# w65c265sxb_controller.net
KiCad netlist of a schematic drawn in EAGLE
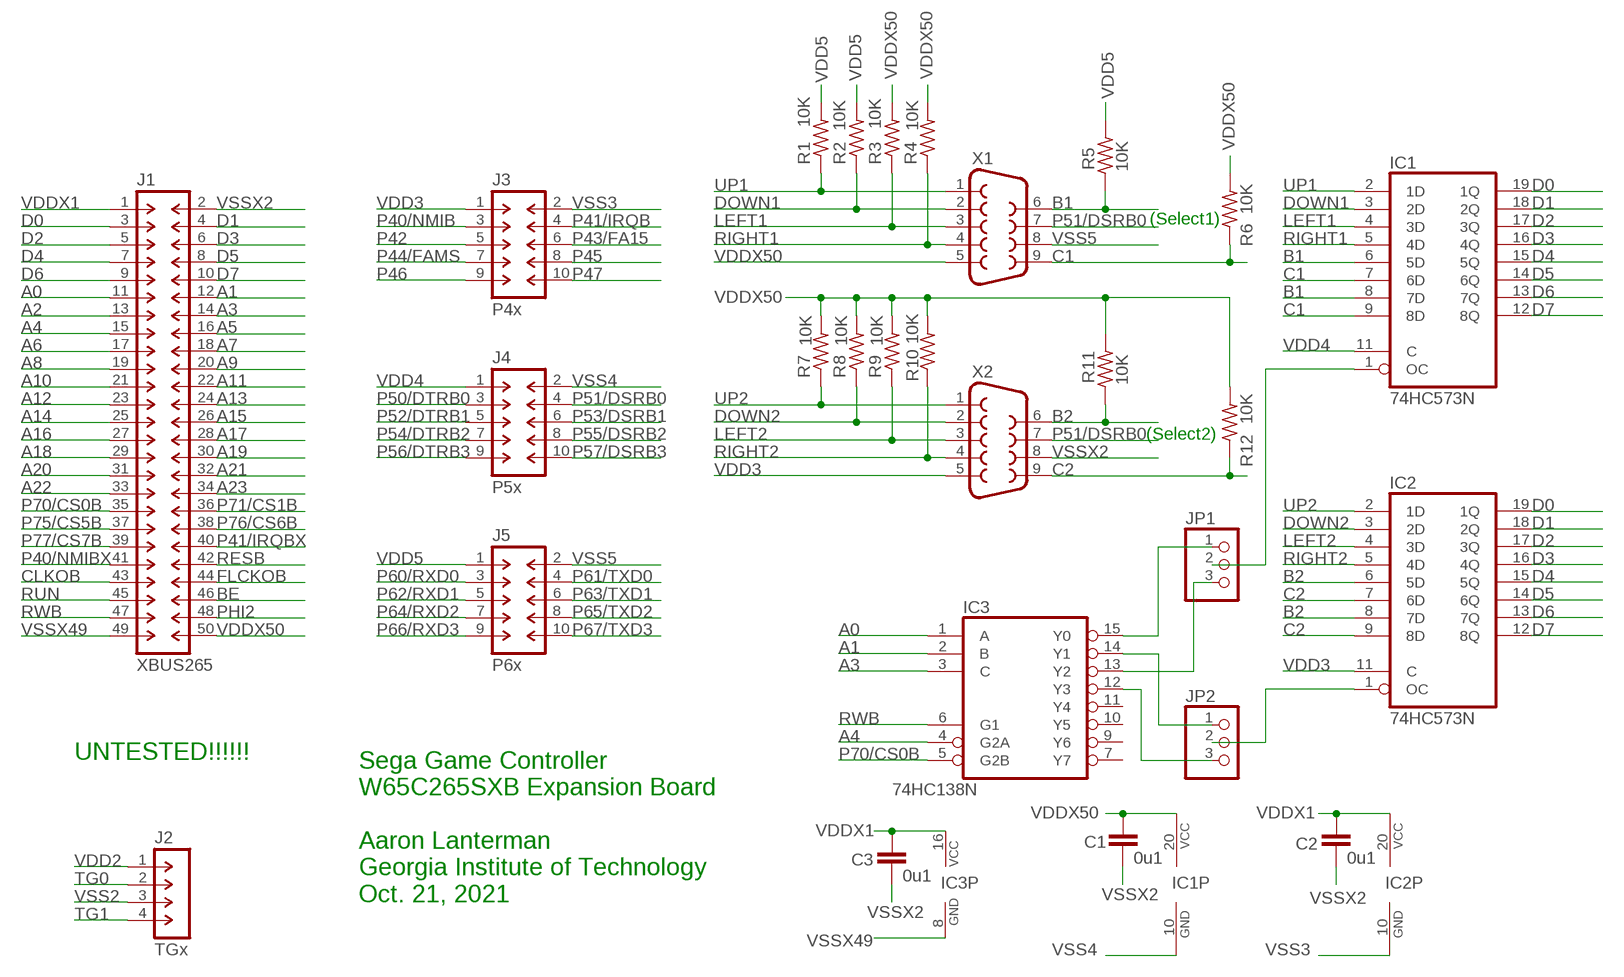
[diagram p0: schematic, sheet 1]

(export (version "E")
  (design (tool "Eeschema 10.0.6"))
  (components
    (comp (ref "C1")
      (value "0u1")
      (footprint "eagle-import:C050-025X075-AARON")
      (libsource (lib "eagle-import") (part "C-EU050-025X075-AARON"))
    )
    (comp (ref "C2")
      (value "0u1")
      (footprint "eagle-import:C050-025X075-AARON")
      (libsource (lib "eagle-import") (part "C-EU050-025X075-AARON"))
    )
    (comp (ref "C3")
      (value "0u1")
      (footprint "eagle-import:C050-025X075-AARON")
      (libsource (lib "eagle-import") (part "C-EU050-025X075-AARON"))
    )
    (comp (ref "IC1")
      (value "74HC573N")
      (footprint "eagle-import:DIL20")
      (libsource (lib "eagle-import") (part "74573NHC"))
    )
    (comp (ref "IC2")
      (value "74HC573N")
      (footprint "eagle-import:DIL20")
      (libsource (lib "eagle-import") (part "74573NHC"))
    )
    (comp (ref "IC3")
      (value "74HC138N")
      (footprint "eagle-import:DIL16")
      (libsource (lib "eagle-import") (part "74138NHC"))
    )
    (comp (ref "J1")
      (value "XBUS265")
      (footprint "eagle-import:DIL-100-2X25")
      (libsource (lib "eagle-import") (part "M-2X25-DIL-100"))
    )
    (comp (ref "J2")
      (value "TGx")
      (footprint "eagle-import:SIP-100-04-40")
      (libsource (lib "eagle-import") (part "M-1X04-SIP-100-40"))
    )
    (comp (ref "J3")
      (value "P4x")
      (footprint "eagle-import:DIL-100-2X05")
      (libsource (lib "eagle-import") (part "M-2X05-DIL-100"))
    )
    (comp (ref "J4")
      (value "P5x")
      (footprint "eagle-import:DIL-100-2X05")
      (libsource (lib "eagle-import") (part "M-2X05-DIL-100"))
    )
    (comp (ref "J5")
      (value "P6x")
      (footprint "eagle-import:DIL-100-2X05")
      (libsource (lib "eagle-import") (part "M-2X05-DIL-100"))
    )
    (comp (ref "JP1")
      (value "PINHD-1X3")
      (footprint "eagle-import:1X03")
      (libsource (lib "eagle-import") (part "PINHD-1X3"))
    )
    (comp (ref "JP2")
      (value "PINHD-1X3")
      (footprint "eagle-import:1X03")
      (libsource (lib "eagle-import") (part "PINHD-1X3"))
    )
    (comp (ref "R1")
      (value "10K")
      (footprint "eagle-import:0207_10")
      (libsource (lib "eagle-import") (part "R-US_0207/10"))
    )
    (comp (ref "R2")
      (value "10K")
      (footprint "eagle-import:0207_10")
      (libsource (lib "eagle-import") (part "R-US_0207/10"))
    )
    (comp (ref "R3")
      (value "10K")
      (footprint "eagle-import:0207_10")
      (libsource (lib "eagle-import") (part "R-US_0207/10"))
    )
    (comp (ref "R4")
      (value "10K")
      (footprint "eagle-import:0207_10")
      (libsource (lib "eagle-import") (part "R-US_0207/10"))
    )
    (comp (ref "R5")
      (value "10K")
      (footprint "eagle-import:0207_10")
      (libsource (lib "eagle-import") (part "R-US_0207/10"))
    )
    (comp (ref "R6")
      (value "10K")
      (footprint "eagle-import:0207_10")
      (libsource (lib "eagle-import") (part "R-US_0207/10"))
    )
    (comp (ref "R7")
      (value "10K")
      (footprint "eagle-import:0207_10")
      (libsource (lib "eagle-import") (part "R-US_0207/10"))
    )
    (comp (ref "R8")
      (value "10K")
      (footprint "eagle-import:0207_10")
      (libsource (lib "eagle-import") (part "R-US_0207/10"))
    )
    (comp (ref "R9")
      (value "10K")
      (footprint "eagle-import:0207_10")
      (libsource (lib "eagle-import") (part "R-US_0207/10"))
    )
    (comp (ref "R10")
      (value "10K")
      (footprint "eagle-import:0207_10")
      (libsource (lib "eagle-import") (part "R-US_0207/10"))
    )
    (comp (ref "R11")
      (value "10K")
      (footprint "eagle-import:0207_10")
      (libsource (lib "eagle-import") (part "R-US_0207/10"))
    )
    (comp (ref "R12")
      (value "10K")
      (footprint "eagle-import:0207_10")
      (libsource (lib "eagle-import") (part "R-US_0207/10"))
    )
    (comp (ref "X1")
      (value "F09HP")
      (footprint "eagle-import:F09HP")
      (libsource (lib "eagle-import") (part "F09HP"))
    )
    (comp (ref "X2")
      (value "F09HP")
      (footprint "eagle-import:F09HP")
      (libsource (lib "eagle-import") (part "F09HP"))
    )
  )
  (nets
    (net (code "1") (name "/A0") (class "Default")
      (node (ref "IC3") (pin "1") (pinfunction "A_1") (pintype "input"))
      (node (ref "J1") (pin "11") (pinfunction "11_11") (pintype "passive"))
    )
    (net (code "2") (name "/A1") (class "Default")
      (node (ref "IC3") (pin "2") (pinfunction "B_2") (pintype "input"))
      (node (ref "J1") (pin "12") (pinfunction "12_12") (pintype "passive"))
    )
    (net (code "3") (name "/A2") (class "Default")
      (node (ref "J1") (pin "13") (pinfunction "13_13") (pintype "passive"))
    )
    (net (code "4") (name "/A3") (class "Default")
      (node (ref "IC3") (pin "3") (pinfunction "C_3") (pintype "input"))
      (node (ref "J1") (pin "14") (pinfunction "14_14") (pintype "passive"))
    )
    (net (code "5") (name "/A4") (class "Default")
      (node (ref "IC3") (pin "4") (pinfunction "G2A_4") (pintype "input"))
      (node (ref "J1") (pin "15") (pinfunction "15_15") (pintype "passive"))
    )
    (net (code "6") (name "/A5") (class "Default")
      (node (ref "J1") (pin "16") (pinfunction "16_16") (pintype "passive"))
    )
    (net (code "7") (name "/A6") (class "Default")
      (node (ref "J1") (pin "17") (pinfunction "17_17") (pintype "passive"))
    )
    (net (code "8") (name "/A7") (class "Default")
      (node (ref "J1") (pin "18") (pinfunction "18_18") (pintype "passive"))
    )
    (net (code "9") (name "/A8") (class "Default")
      (node (ref "J1") (pin "19") (pinfunction "19_19") (pintype "passive"))
    )
    (net (code "10") (name "/A9") (class "Default")
      (node (ref "J1") (pin "20") (pinfunction "20_20") (pintype "passive"))
    )
    (net (code "11") (name "/A10") (class "Default")
      (node (ref "J1") (pin "21") (pinfunction "21_21") (pintype "passive"))
    )
    (net (code "12") (name "/A11") (class "Default")
      (node (ref "J1") (pin "22") (pinfunction "22_22") (pintype "passive"))
    )
    (net (code "13") (name "/A12") (class "Default")
      (node (ref "J1") (pin "23") (pinfunction "23_23") (pintype "passive"))
    )
    (net (code "14") (name "/A13") (class "Default")
      (node (ref "J1") (pin "24") (pinfunction "24_24") (pintype "passive"))
    )
    (net (code "15") (name "/A14") (class "Default")
      (node (ref "J1") (pin "25") (pinfunction "25_25") (pintype "passive"))
    )
    (net (code "16") (name "/A15") (class "Default")
      (node (ref "J1") (pin "26") (pinfunction "26_26") (pintype "passive"))
    )
    (net (code "17") (name "/A16") (class "Default")
      (node (ref "J1") (pin "27") (pinfunction "27_27") (pintype "passive"))
    )
    (net (code "18") (name "/A17") (class "Default")
      (node (ref "J1") (pin "28") (pinfunction "28_28") (pintype "passive"))
    )
    (net (code "19") (name "/A18") (class "Default")
      (node (ref "J1") (pin "29") (pinfunction "29_29") (pintype "passive"))
    )
    (net (code "20") (name "/A19") (class "Default")
      (node (ref "J1") (pin "30") (pinfunction "30_30") (pintype "passive"))
    )
    (net (code "21") (name "/A20") (class "Default")
      (node (ref "J1") (pin "31") (pinfunction "31_31") (pintype "passive"))
    )
    (net (code "22") (name "/A21") (class "Default")
      (node (ref "J1") (pin "32") (pinfunction "32_32") (pintype "passive"))
    )
    (net (code "23") (name "/A22") (class "Default")
      (node (ref "J1") (pin "33") (pinfunction "33_33") (pintype "passive"))
    )
    (net (code "24") (name "/A23") (class "Default")
      (node (ref "J1") (pin "34") (pinfunction "34_34") (pintype "passive"))
    )
    (net (code "25") (name "/B1") (class "Default")
      (node (ref "IC1") (pin "6") (pinfunction "5D_6") (pintype "input"))
      (node (ref "IC1") (pin "8") (pinfunction "7D_8") (pintype "input"))
      (node (ref "R5") (pin "1") (pinfunction "1_1") (pintype "passive"))
      (node (ref "X1") (pin "6") (pinfunction "6_6") (pintype "passive"))
    )
    (net (code "26") (name "/B2") (class "Default")
      (node (ref "IC2") (pin "6") (pinfunction "5D_6") (pintype "input"))
      (node (ref "IC2") (pin "8") (pinfunction "7D_8") (pintype "input"))
      (node (ref "R11") (pin "1") (pinfunction "1_1") (pintype "passive"))
      (node (ref "X2") (pin "6") (pinfunction "6_6") (pintype "passive"))
    )
    (net (code "27") (name "/BE") (class "Default")
      (node (ref "J1") (pin "46") (pinfunction "46_46") (pintype "passive"))
    )
    (net (code "28") (name "/C1") (class "Default")
      (node (ref "IC1") (pin "7") (pinfunction "6D_7") (pintype "input"))
      (node (ref "IC1") (pin "9") (pinfunction "8D_9") (pintype "input"))
      (node (ref "R6") (pin "1") (pinfunction "1_1") (pintype "passive"))
      (node (ref "X1") (pin "9") (pinfunction "9_9") (pintype "passive"))
    )
    (net (code "29") (name "/C2") (class "Default")
      (node (ref "IC2") (pin "7") (pinfunction "6D_7") (pintype "input"))
      (node (ref "IC2") (pin "9") (pinfunction "8D_9") (pintype "input"))
      (node (ref "R12") (pin "1") (pinfunction "1_1") (pintype "passive"))
      (node (ref "X2") (pin "9") (pinfunction "9_9") (pintype "passive"))
    )
    (net (code "30") (name "/CLKOB") (class "Default")
      (node (ref "J1") (pin "43") (pinfunction "43_43") (pintype "passive"))
    )
    (net (code "31") (name "/D0") (class "Default")
      (node (ref "IC1") (pin "19") (pinfunction "1Q_19") (pintype "tri_state"))
      (node (ref "IC2") (pin "19") (pinfunction "1Q_19") (pintype "tri_state"))
      (node (ref "J1") (pin "3") (pinfunction "3_3") (pintype "passive"))
    )
    (net (code "32") (name "/D1") (class "Default")
      (node (ref "IC1") (pin "18") (pinfunction "2Q_18") (pintype "tri_state"))
      (node (ref "IC2") (pin "18") (pinfunction "2Q_18") (pintype "tri_state"))
      (node (ref "J1") (pin "4") (pinfunction "4_4") (pintype "passive"))
    )
    (net (code "33") (name "/D2") (class "Default")
      (node (ref "IC1") (pin "17") (pinfunction "3Q_17") (pintype "tri_state"))
      (node (ref "IC2") (pin "17") (pinfunction "3Q_17") (pintype "tri_state"))
      (node (ref "J1") (pin "5") (pinfunction "5_5") (pintype "passive"))
    )
    (net (code "34") (name "/D3") (class "Default")
      (node (ref "IC1") (pin "16") (pinfunction "4Q_16") (pintype "tri_state"))
      (node (ref "IC2") (pin "16") (pinfunction "4Q_16") (pintype "tri_state"))
      (node (ref "J1") (pin "6") (pinfunction "6_6") (pintype "passive"))
    )
    (net (code "35") (name "/D4") (class "Default")
      (node (ref "IC1") (pin "15") (pinfunction "5Q_15") (pintype "tri_state"))
      (node (ref "IC2") (pin "15") (pinfunction "5Q_15") (pintype "tri_state"))
      (node (ref "J1") (pin "7") (pinfunction "7_7") (pintype "passive"))
    )
    (net (code "36") (name "/D5") (class "Default")
      (node (ref "IC1") (pin "14") (pinfunction "6Q_14") (pintype "tri_state"))
      (node (ref "IC2") (pin "14") (pinfunction "6Q_14") (pintype "tri_state"))
      (node (ref "J1") (pin "8") (pinfunction "8_8") (pintype "passive"))
    )
    (net (code "37") (name "/D6") (class "Default")
      (node (ref "IC1") (pin "13") (pinfunction "7Q_13") (pintype "tri_state"))
      (node (ref "IC2") (pin "13") (pinfunction "7Q_13") (pintype "tri_state"))
      (node (ref "J1") (pin "9") (pinfunction "9_9") (pintype "passive"))
    )
    (net (code "38") (name "/D7") (class "Default")
      (node (ref "IC1") (pin "12") (pinfunction "8Q_12") (pintype "tri_state"))
      (node (ref "IC2") (pin "12") (pinfunction "8Q_12") (pintype "tri_state"))
      (node (ref "J1") (pin "10") (pinfunction "10_10") (pintype "passive"))
    )
    (net (code "39") (name "/DOWN1") (class "Default")
      (node (ref "IC1") (pin "3") (pinfunction "2D_3") (pintype "input"))
      (node (ref "R2") (pin "1") (pinfunction "1_1") (pintype "passive"))
      (node (ref "X1") (pin "2") (pinfunction "2_2") (pintype "passive"))
    )
    (net (code "40") (name "/DOWN2") (class "Default")
      (node (ref "IC2") (pin "3") (pinfunction "2D_3") (pintype "input"))
      (node (ref "R8") (pin "1") (pinfunction "1_1") (pintype "passive"))
      (node (ref "X2") (pin "2") (pinfunction "2_2") (pintype "passive"))
    )
    (net (code "41") (name "/FLCKOB") (class "Default")
      (node (ref "J1") (pin "44") (pinfunction "44_44") (pintype "passive"))
    )
    (net (code "42") (name "/LEFT1") (class "Default")
      (node (ref "IC1") (pin "4") (pinfunction "3D_4") (pintype "input"))
      (node (ref "R3") (pin "1") (pinfunction "1_1") (pintype "passive"))
      (node (ref "X1") (pin "3") (pinfunction "3_3") (pintype "passive"))
    )
    (net (code "43") (name "/LEFT2") (class "Default")
      (node (ref "IC2") (pin "4") (pinfunction "3D_4") (pintype "input"))
      (node (ref "R9") (pin "1") (pinfunction "1_1") (pintype "passive"))
      (node (ref "X2") (pin "3") (pinfunction "3_3") (pintype "passive"))
    )
    (net (code "44") (name "/P40{slash}NMIB") (class "Default")
      (node (ref "J3") (pin "3") (pinfunction "3_3") (pintype "passive"))
    )
    (net (code "45") (name "/P40{slash}NMIBX") (class "Default")
      (node (ref "J1") (pin "41") (pinfunction "41_41") (pintype "passive"))
    )
    (net (code "46") (name "/P41{slash}IRQB") (class "Default")
      (node (ref "J3") (pin "4") (pinfunction "4_4") (pintype "passive"))
    )
    (net (code "47") (name "/P41{slash}IRQBX") (class "Default")
      (node (ref "J1") (pin "40") (pinfunction "40_40") (pintype "passive"))
    )
    (net (code "48") (name "/P42") (class "Default")
      (node (ref "J3") (pin "5") (pinfunction "5_5") (pintype "passive"))
    )
    (net (code "49") (name "/P43{slash}FA15") (class "Default")
      (node (ref "J3") (pin "6") (pinfunction "6_6") (pintype "passive"))
    )
    (net (code "50") (name "/P44{slash}FAMS") (class "Default")
      (node (ref "J3") (pin "7") (pinfunction "7_7") (pintype "passive"))
    )
    (net (code "51") (name "/P45") (class "Default")
      (node (ref "J3") (pin "8") (pinfunction "8_8") (pintype "passive"))
    )
    (net (code "52") (name "/P46") (class "Default")
      (node (ref "J3") (pin "9") (pinfunction "9_9") (pintype "passive"))
    )
    (net (code "53") (name "/P47") (class "Default")
      (node (ref "J3") (pin "10") (pinfunction "10_10") (pintype "passive"))
    )
    (net (code "54") (name "/P50{slash}DTRB0") (class "Default")
      (node (ref "J4") (pin "3") (pinfunction "3_3") (pintype "passive"))
    )
    (net (code "55") (name "/P51{slash}DSRB0") (class "Default")
      (node (ref "J4") (pin "4") (pinfunction "4_4") (pintype "passive"))
      (node (ref "X1") (pin "7") (pinfunction "7_7") (pintype "passive"))
      (node (ref "X2") (pin "7") (pinfunction "7_7") (pintype "passive"))
    )
    (net (code "56") (name "/P52{slash}DTRB1") (class "Default")
      (node (ref "J4") (pin "5") (pinfunction "5_5") (pintype "passive"))
    )
    (net (code "57") (name "/P53{slash}DSRB1") (class "Default")
      (node (ref "J4") (pin "6") (pinfunction "6_6") (pintype "passive"))
    )
    (net (code "58") (name "/P54{slash}DTRB2") (class "Default")
      (node (ref "J4") (pin "7") (pinfunction "7_7") (pintype "passive"))
    )
    (net (code "59") (name "/P55{slash}DSRB2") (class "Default")
      (node (ref "J4") (pin "8") (pinfunction "8_8") (pintype "passive"))
    )
    (net (code "60") (name "/P56{slash}DTRB3") (class "Default")
      (node (ref "J4") (pin "9") (pinfunction "9_9") (pintype "passive"))
    )
    (net (code "61") (name "/P57{slash}DSRB3") (class "Default")
      (node (ref "J4") (pin "10") (pinfunction "10_10") (pintype "passive"))
    )
    (net (code "62") (name "/P60{slash}RXD0") (class "Default")
      (node (ref "J5") (pin "3") (pinfunction "3_3") (pintype "passive"))
    )
    (net (code "63") (name "/P61{slash}TXD0") (class "Default")
      (node (ref "J5") (pin "4") (pinfunction "4_4") (pintype "passive"))
    )
    (net (code "64") (name "/P62{slash}RXD1") (class "Default")
      (node (ref "J5") (pin "5") (pinfunction "5_5") (pintype "passive"))
    )
    (net (code "65") (name "/P63{slash}TXD1") (class "Default")
      (node (ref "J5") (pin "6") (pinfunction "6_6") (pintype "passive"))
    )
    (net (code "66") (name "/P64{slash}RXD2") (class "Default")
      (node (ref "J5") (pin "7") (pinfunction "7_7") (pintype "passive"))
    )
    (net (code "67") (name "/P65{slash}TXD2") (class "Default")
      (node (ref "J5") (pin "8") (pinfunction "8_8") (pintype "passive"))
    )
    (net (code "68") (name "/P66{slash}RXD3") (class "Default")
      (node (ref "J5") (pin "9") (pinfunction "9_9") (pintype "passive"))
    )
    (net (code "69") (name "/P67{slash}TXD3") (class "Default")
      (node (ref "J5") (pin "10") (pinfunction "10_10") (pintype "passive"))
    )
    (net (code "70") (name "/P70{slash}CS0B") (class "Default")
      (node (ref "IC3") (pin "5") (pinfunction "G2B_5") (pintype "input"))
      (node (ref "J1") (pin "35") (pinfunction "35_35") (pintype "passive"))
    )
    (net (code "71") (name "/P71{slash}CS1B") (class "Default")
      (node (ref "J1") (pin "36") (pinfunction "36_36") (pintype "passive"))
    )
    (net (code "72") (name "/P75{slash}CS5B") (class "Default")
      (node (ref "J1") (pin "37") (pinfunction "37_37") (pintype "passive"))
    )
    (net (code "73") (name "/P76{slash}CS6B") (class "Default")
      (node (ref "J1") (pin "38") (pinfunction "38_38") (pintype "passive"))
    )
    (net (code "74") (name "/P77{slash}CS7B") (class "Default")
      (node (ref "J1") (pin "39") (pinfunction "39_39") (pintype "passive"))
    )
    (net (code "75") (name "/PHI2") (class "Default")
      (node (ref "J1") (pin "48") (pinfunction "48_48") (pintype "passive"))
    )
    (net (code "76") (name "/RESB") (class "Default")
      (node (ref "J1") (pin "42") (pinfunction "42_42") (pintype "passive"))
    )
    (net (code "77") (name "/RIGHT1") (class "Default")
      (node (ref "IC1") (pin "5") (pinfunction "4D_5") (pintype "input"))
      (node (ref "R4") (pin "1") (pinfunction "1_1") (pintype "passive"))
      (node (ref "X1") (pin "4") (pinfunction "4_4") (pintype "passive"))
    )
    (net (code "78") (name "/RIGHT2") (class "Default")
      (node (ref "IC2") (pin "5") (pinfunction "4D_5") (pintype "input"))
      (node (ref "R10") (pin "1") (pinfunction "1_1") (pintype "passive"))
      (node (ref "X2") (pin "4") (pinfunction "4_4") (pintype "passive"))
    )
    (net (code "79") (name "/RUN") (class "Default")
      (node (ref "J1") (pin "45") (pinfunction "45_45") (pintype "passive"))
    )
    (net (code "80") (name "/RWB") (class "Default")
      (node (ref "IC3") (pin "6") (pinfunction "G1_6") (pintype "input"))
      (node (ref "J1") (pin "47") (pinfunction "47_47") (pintype "passive"))
    )
    (net (code "81") (name "/TG0") (class "Default")
      (node (ref "J2") (pin "2") (pinfunction "2_2") (pintype "passive"))
    )
    (net (code "82") (name "/TG1") (class "Default")
      (node (ref "J2") (pin "4") (pinfunction "4_4") (pintype "passive"))
    )
    (net (code "83") (name "/UP1") (class "Default")
      (node (ref "IC1") (pin "2") (pinfunction "1D_2") (pintype "input"))
      (node (ref "R1") (pin "1") (pinfunction "1_1") (pintype "passive"))
      (node (ref "X1") (pin "1") (pinfunction "1_1") (pintype "passive"))
    )
    (net (code "84") (name "/UP2") (class "Default")
      (node (ref "IC2") (pin "2") (pinfunction "1D_2") (pintype "input"))
      (node (ref "R7") (pin "1") (pinfunction "1_1") (pintype "passive"))
      (node (ref "X2") (pin "1") (pinfunction "1_1") (pintype "passive"))
    )
    (net (code "85") (name "/VDD2") (class "Default")
      (node (ref "J2") (pin "1") (pinfunction "1_1") (pintype "passive"))
    )
    (net (code "86") (name "/VDD3") (class "Default")
      (node (ref "IC2") (pin "11") (pinfunction "C_11") (pintype "input"))
      (node (ref "J3") (pin "1") (pinfunction "1_1") (pintype "passive"))
      (node (ref "X2") (pin "5") (pinfunction "5_5") (pintype "passive"))
    )
    (net (code "87") (name "/VDD4") (class "Default")
      (node (ref "IC1") (pin "11") (pinfunction "C_11") (pintype "input"))
      (node (ref "J4") (pin "1") (pinfunction "1_1") (pintype "passive"))
    )
    (net (code "88") (name "/VDD5") (class "Default")
      (node (ref "J5") (pin "1") (pinfunction "1_1") (pintype "passive"))
      (node (ref "R1") (pin "2") (pinfunction "2_2") (pintype "passive"))
      (node (ref "R2") (pin "2") (pinfunction "2_2") (pintype "passive"))
      (node (ref "R5") (pin "2") (pinfunction "2_2") (pintype "passive"))
    )
    (net (code "89") (name "/VDDX1") (class "Default")
      (node (ref "C2") (pin "1") (pinfunction "1_1") (pintype "passive"))
      (node (ref "C3") (pin "1") (pinfunction "1_1") (pintype "passive"))
      (node (ref "IC2") (pin "20") (pinfunction "VCC_20") (pintype "power_in"))
      (node (ref "IC3") (pin "16") (pinfunction "VCC_16") (pintype "power_in"))
      (node (ref "J1") (pin "1") (pinfunction "1_1") (pintype "passive"))
    )
    (net (code "90") (name "/VDDX50") (class "Default")
      (node (ref "C1") (pin "1") (pinfunction "1_1") (pintype "passive"))
      (node (ref "IC1") (pin "20") (pinfunction "VCC_20") (pintype "power_in"))
      (node (ref "J1") (pin "50") (pinfunction "50_50") (pintype "passive"))
      (node (ref "R10") (pin "2") (pinfunction "2_2") (pintype "passive"))
      (node (ref "R11") (pin "2") (pinfunction "2_2") (pintype "passive"))
      (node (ref "R12") (pin "2") (pinfunction "2_2") (pintype "passive"))
      (node (ref "R3") (pin "2") (pinfunction "2_2") (pintype "passive"))
      (node (ref "R4") (pin "2") (pinfunction "2_2") (pintype "passive"))
      (node (ref "R6") (pin "2") (pinfunction "2_2") (pintype "passive"))
      (node (ref "R7") (pin "2") (pinfunction "2_2") (pintype "passive"))
      (node (ref "R8") (pin "2") (pinfunction "2_2") (pintype "passive"))
      (node (ref "R9") (pin "2") (pinfunction "2_2") (pintype "passive"))
      (node (ref "X1") (pin "5") (pinfunction "5_5") (pintype "passive"))
    )
    (net (code "91") (name "/VSS2") (class "Default")
      (node (ref "J2") (pin "3") (pinfunction "3_3") (pintype "passive"))
    )
    (net (code "92") (name "/VSS3") (class "Default")
      (node (ref "IC2") (pin "10") (pinfunction "GND_10") (pintype "power_in"))
      (node (ref "J3") (pin "2") (pinfunction "2_2") (pintype "passive"))
    )
    (net (code "93") (name "/VSS4") (class "Default")
      (node (ref "IC1") (pin "10") (pinfunction "GND_10") (pintype "power_in"))
      (node (ref "J4") (pin "2") (pinfunction "2_2") (pintype "passive"))
    )
    (net (code "94") (name "/VSS5") (class "Default")
      (node (ref "J5") (pin "2") (pinfunction "2_2") (pintype "passive"))
      (node (ref "X1") (pin "8") (pinfunction "8_8") (pintype "passive"))
    )
    (net (code "95") (name "/VSSX2") (class "Default")
      (node (ref "C1") (pin "2") (pinfunction "2_2") (pintype "passive"))
      (node (ref "C2") (pin "2") (pinfunction "2_2") (pintype "passive"))
      (node (ref "C3") (pin "2") (pinfunction "2_2") (pintype "passive"))
      (node (ref "J1") (pin "2") (pinfunction "2_2") (pintype "passive"))
      (node (ref "X2") (pin "8") (pinfunction "8_8") (pintype "passive"))
    )
    (net (code "96") (name "/VSSX49") (class "Default")
      (node (ref "IC3") (pin "8") (pinfunction "GND_8") (pintype "power_in"))
      (node (ref "J1") (pin "49") (pinfunction "49_49") (pintype "passive"))
    )
    (net (code "97") (name "Net-(IC1A-OC)") (class "Default")
      (node (ref "IC1") (pin "1") (pinfunction "OC_1") (pintype "input"))
      (node (ref "JP1") (pin "2") (pinfunction "2_2") (pintype "passive"))
    )
    (net (code "98") (name "Net-(IC2A-OC)") (class "Default")
      (node (ref "IC2") (pin "1") (pinfunction "OC_1") (pintype "input"))
      (node (ref "JP2") (pin "2") (pinfunction "2_2") (pintype "passive"))
    )
    (net (code "99") (name "Net-(IC3A-Y0)") (class "Default")
      (node (ref "IC3") (pin "15") (pinfunction "Y0_15") (pintype "output"))
      (node (ref "JP1") (pin "1") (pinfunction "1_1") (pintype "passive"))
    )
    (net (code "100") (name "Net-(IC3A-Y1)") (class "Default")
      (node (ref "IC3") (pin "14") (pinfunction "Y1_14") (pintype "output"))
      (node (ref "JP2") (pin "1") (pinfunction "1_1") (pintype "passive"))
    )
    (net (code "101") (name "Net-(IC3A-Y2)") (class "Default")
      (node (ref "IC3") (pin "13") (pinfunction "Y2_13") (pintype "output"))
      (node (ref "JP1") (pin "3") (pinfunction "3_3") (pintype "passive"))
    )
    (net (code "102") (name "Net-(IC3A-Y3)") (class "Default")
      (node (ref "IC3") (pin "12") (pinfunction "Y3_12") (pintype "output"))
      (node (ref "JP2") (pin "3") (pinfunction "3_3") (pintype "passive"))
    )
    (net (code "103") (name "unconnected-(IC3A-Y4-Pad11)") (class "Default")
      (node (ref "IC3") (pin "11") (pinfunction "Y4_11") (pintype "output"))
    )
    (net (code "104") (name "unconnected-(IC3A-Y5-Pad10)") (class "Default")
      (node (ref "IC3") (pin "10") (pinfunction "Y5_10") (pintype "output"))
    )
    (net (code "105") (name "unconnected-(IC3A-Y6-Pad9)") (class "Default")
      (node (ref "IC3") (pin "9") (pinfunction "Y6_9") (pintype "output"))
    )
    (net (code "106") (name "unconnected-(IC3A-Y7-Pad7)") (class "Default")
      (node (ref "IC3") (pin "7") (pinfunction "Y7_7") (pintype "output"))
    )
  )
)
